# HV_Interlock_Circuit.net
KiCad netlist of a schematic drawn in Altium Designer
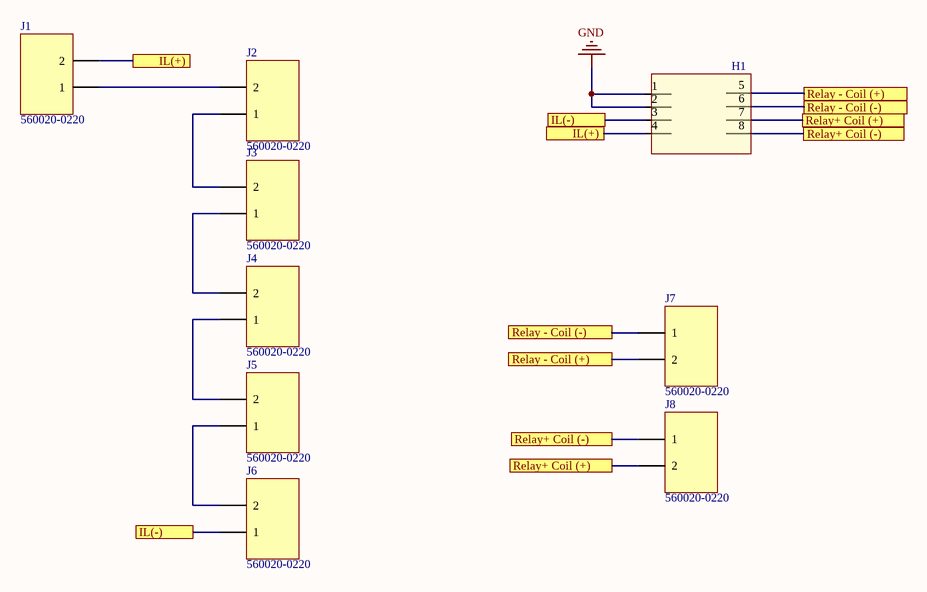
[diagram p0: HV Interlock Circuit.SchDoc]

(export (version "E")
  (design (tool "Eeschema 10.0.6"))
  (components
    (comp (ref "H1")
      (value "TE-1379684-1")
      (footprint "TE-1379684-1")
      (libsource (lib "Thermal Management System Altium Library_v01") (part "TE-1379684-1"))
    )
    (comp (ref "J1")
      (value "560020-0220")
      (footprint "560020-0220")
      (description "CONN HEADER SMD 2POS 2MM")
      (fields (field (name "MANUFACTURER") "Molex"))
      (libsource (lib "") (part "560020-0220_2"))
    )
    (comp (ref "J2")
      (value "560020-0220")
      (footprint "560020-0220")
      (description "CONN HEADER SMD 2POS 2MM")
      (fields (field (name "MANUFACTURER") "Molex"))
      (libsource (lib "") (part "560020-0220_1"))
    )
    (comp (ref "J3")
      (value "560020-0220")
      (footprint "560020-0220")
      (description "CONN HEADER SMD 2POS 2MM")
      (fields (field (name "MANUFACTURER") "Molex"))
      (libsource (lib "") (part "560020-0220_1"))
    )
    (comp (ref "J4")
      (value "560020-0220")
      (footprint "560020-0220")
      (description "CONN HEADER SMD 2POS 2MM")
      (fields (field (name "MANUFACTURER") "Molex"))
      (libsource (lib "") (part "560020-0220_1"))
    )
    (comp (ref "J5")
      (value "560020-0220")
      (footprint "560020-0220")
      (description "CONN HEADER SMD 2POS 2MM")
      (fields (field (name "MANUFACTURER") "Molex"))
      (libsource (lib "") (part "560020-0220_1"))
    )
    (comp (ref "J6")
      (value "560020-0220")
      (footprint "560020-0220")
      (description "CONN HEADER SMD 2POS 2MM")
      (fields (field (name "MANUFACTURER") "Molex"))
      (libsource (lib "") (part "560020-0220_1"))
    )
    (comp (ref "J7")
      (value "560020-0220")
      (footprint "560020-0220")
      (description "CONN HEADER SMD 2POS 2MM")
      (fields (field (name "MANUFACTURER") "Molex"))
      (libsource (lib "Integrated_Library1") (part "560020-0220"))
    )
    (comp (ref "J8")
      (value "560020-0220")
      (footprint "560020-0220")
      (description "CONN HEADER SMD 2POS 2MM")
      (fields (field (name "MANUFACTURER") "Molex"))
      (libsource (lib "Integrated_Library1") (part "560020-0220"))
    )
  )
  (nets
    (net (code "1") (name "/IL(+)") (class "Default")
      (node (ref "H1") (pin "4") (pinfunction "K_4") (pintype "passive"))
      (node (ref "J1") (pin "2") (pinfunction "2_2") (pintype "passive"))
    )
    (net (code "2") (name "/IL(-)") (class "Default")
      (node (ref "H1") (pin "3") (pinfunction "K_3") (pintype "passive"))
      (node (ref "J6") (pin "1") (pinfunction "1_1") (pintype "passive"))
    )
    (net (code "3") (name "/Relay - Coil (+)") (class "Default")
      (node (ref "H1") (pin "5") (pinfunction "K_5") (pintype "passive"))
      (node (ref "J7") (pin "2") (pinfunction "2_2") (pintype "passive"))
    )
    (net (code "4") (name "/Relay - Coil (-)") (class "Default")
      (node (ref "H1") (pin "6") (pinfunction "K_6") (pintype "passive"))
      (node (ref "J7") (pin "1") (pinfunction "1_1") (pintype "passive"))
    )
    (net (code "5") (name "/Relay+ Coil (+)") (class "Default")
      (node (ref "H1") (pin "7") (pinfunction "K_7") (pintype "passive"))
      (node (ref "J8") (pin "2") (pinfunction "2_2") (pintype "passive"))
    )
    (net (code "6") (name "/Relay+ Coil (-)") (class "Default")
      (node (ref "H1") (pin "8") (pinfunction "K_8") (pintype "passive"))
      (node (ref "J8") (pin "1") (pinfunction "1_1") (pintype "passive"))
    )
    (net (code "7") (name "GND") (class "Default")
      (node (ref "H1") (pin "1") (pinfunction "K_1") (pintype "passive"))
      (node (ref "H1") (pin "2") (pinfunction "K_2") (pintype "passive"))
    )
    (net (code "8") (name "Net-(J1-Pad1)") (class "Default")
      (node (ref "J1") (pin "1") (pinfunction "1_1") (pintype "passive"))
      (node (ref "J2") (pin "2") (pinfunction "2_2") (pintype "passive"))
    )
    (net (code "9") (name "Net-(J2-Pad1)") (class "Default")
      (node (ref "J2") (pin "1") (pinfunction "1_1") (pintype "passive"))
      (node (ref "J3") (pin "2") (pinfunction "2_2") (pintype "passive"))
    )
    (net (code "10") (name "Net-(J3-Pad1)") (class "Default")
      (node (ref "J3") (pin "1") (pinfunction "1_1") (pintype "passive"))
      (node (ref "J4") (pin "2") (pinfunction "2_2") (pintype "passive"))
    )
    (net (code "11") (name "Net-(J4-Pad1)") (class "Default")
      (node (ref "J4") (pin "1") (pinfunction "1_1") (pintype "passive"))
      (node (ref "J5") (pin "2") (pinfunction "2_2") (pintype "passive"))
    )
    (net (code "12") (name "Net-(J5-Pad1)") (class "Default")
      (node (ref "J5") (pin "1") (pinfunction "1_1") (pintype "passive"))
      (node (ref "J6") (pin "2") (pinfunction "2_2") (pintype "passive"))
    )
  )
)
